# ece411-t04-filamint-V5_2.net
KiCad netlist of a schematic drawn in EAGLE
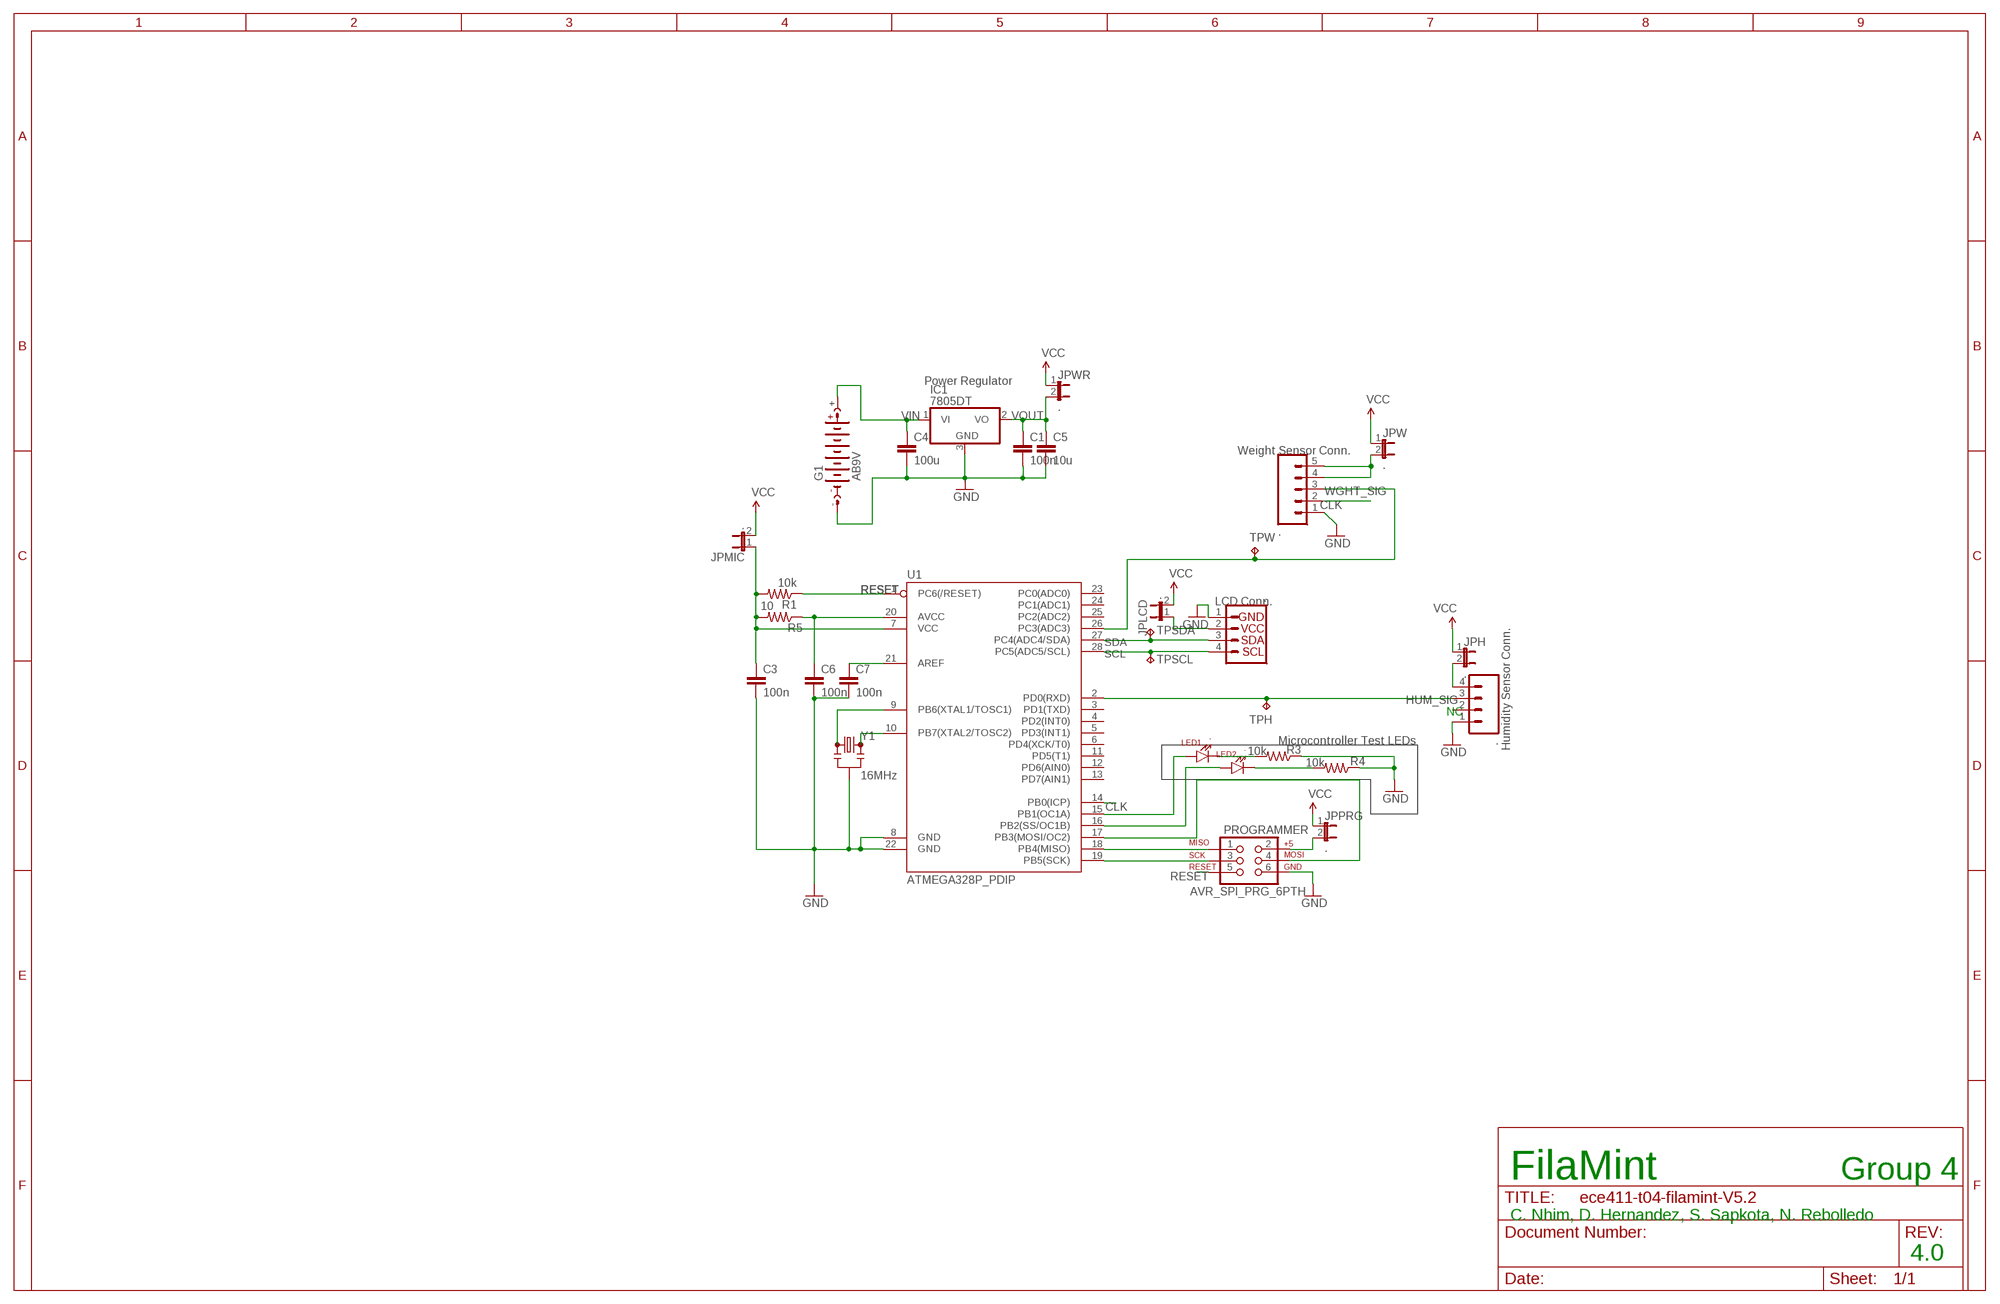
[diagram p0: schematic, sheet 1]

(export (version "E")
  (design (tool "Eeschema 10.0.6"))
  (components
    (comp (ref "C1")
      (value "100n")
      (footprint "eagle-import:C0805")
      (libsource (lib "eagle-import") (part "C-EUC0805"))
    )
    (comp (ref "C3")
      (value "100n")
      (footprint "eagle-import:C0805")
      (libsource (lib "eagle-import") (part "C-EUC0805"))
    )
    (comp (ref "C4")
      (value "100u")
      (footprint "eagle-import:C025-024X044")
      (libsource (lib "eagle-import") (part "C-EU025-024X044"))
    )
    (comp (ref "C5")
      (value "10u")
      (footprint "eagle-import:C025-024X044")
      (libsource (lib "eagle-import") (part "C-EU025-024X044"))
    )
    (comp (ref "C6")
      (value "100n")
      (footprint "eagle-import:C0805")
      (libsource (lib "eagle-import") (part "C-EUC0805"))
    )
    (comp (ref "C7")
      (value "100n")
      (footprint "eagle-import:C0805")
      (libsource (lib "eagle-import") (part "C-EUC0805"))
    )
    (comp (ref "DHT22")
      (value ".")
      (footprint "eagle-import:1X04-1MM-RA")
      (libsource (lib "eagle-import") (part "M04SMD2"))
    )
    (comp (ref "G1")
      (value "AB9V")
      (footprint "eagle-import:AB9V")
      (libsource (lib "eagle-import") (part "AB9V"))
    )
    (comp (ref "HX711")
      (value ".")
      (footprint "eagle-import:1X05-1MM")
      (libsource (lib "eagle-import") (part "M05SMD"))
    )
    (comp (ref "IC1")
      (value "7805DT")
      (footprint "eagle-import:TO252")
      (libsource (lib "eagle-import") (part "78DT05"))
    )
    (comp (ref "JPH")
      (value ".")
      (footprint "eagle-import:JP1")
      (libsource (lib "eagle-import") (part "JP1E"))
    )
    (comp (ref "JPLCD")
      (value ".")
      (footprint "eagle-import:JP1")
      (libsource (lib "eagle-import") (part "JP1E"))
    )
    (comp (ref "JPMIC")
      (value ".")
      (footprint "eagle-import:JP1")
      (libsource (lib "eagle-import") (part "JP1E"))
    )
    (comp (ref "JPPRG")
      (value ".")
      (footprint "eagle-import:JP1")
      (libsource (lib "eagle-import") (part "JP1E"))
    )
    (comp (ref "JPW")
      (value ".")
      (footprint "eagle-import:JP1")
      (libsource (lib "eagle-import") (part "JP1E"))
    )
    (comp (ref "JPWR")
      (value ".")
      (footprint "eagle-import:JP1")
      (libsource (lib "eagle-import") (part "JP1E"))
    )
    (comp (ref "LCD")
      (value ".")
      (footprint "eagle-import:1X04")
      (libsource (lib "eagle-import") (part "I2C_STANDARD"))
    )
    (comp (ref "LED1")
      (value ".")
      (footprint "eagle-import:LTE-302")
      (libsource (lib "eagle-import") (part "LTE-302"))
    )
    (comp (ref "LED2")
      (value ".")
      (footprint "eagle-import:LTE-302")
      (libsource (lib "eagle-import") (part "LTE-302"))
    )
    (comp (ref "PROGRAMMER")
      (value "AVR_SPI_PRG_6PTH")
      (footprint "eagle-import:2X3")
      (libsource (lib "eagle-import") (part "AVR_SPI_PRG_6PTH"))
    )
    (comp (ref "R1")
      (value "10k")
      (footprint "eagle-import:0204_5")
      (libsource (lib "eagle-import") (part "R-US_0204/5"))
    )
    (comp (ref "R3")
      (value "10k")
      (footprint "eagle-import:0204_5")
      (libsource (lib "eagle-import") (part "R-US_0204/5"))
    )
    (comp (ref "R4")
      (value "10k")
      (footprint "eagle-import:0204_5")
      (libsource (lib "eagle-import") (part "R-US_0204/5"))
    )
    (comp (ref "R5")
      (value "10")
      (footprint "eagle-import:0204_5")
      (libsource (lib "eagle-import") (part "R-US_0204/5"))
    )
    (comp (ref "TPH")
      (value "TPB1,27")
      (footprint "eagle-import:B1,27")
      (libsource (lib "eagle-import") (part "TPB1,27"))
    )
    (comp (ref "TPSCL")
      (value "TPB1,27")
      (footprint "eagle-import:B1,27")
      (libsource (lib "eagle-import") (part "TPB1,27"))
    )
    (comp (ref "TPSDA")
      (value "TPB1,27")
      (footprint "eagle-import:B1,27")
      (libsource (lib "eagle-import") (part "TPB1,27"))
    )
    (comp (ref "TPW")
      (value "TPB1,27")
      (footprint "eagle-import:B1,27")
      (libsource (lib "eagle-import") (part "TPB1,27"))
    )
    (comp (ref "U1")
      (value "ATMEGA328P_PDIP")
      (footprint "eagle-import:DIL28-3")
      (libsource (lib "eagle-import") (part "ATMEGA328P_PDIP"))
    )
    (comp (ref "Y1")
      (value "16MHz")
      (footprint "eagle-import:RESONATOR-PTH")
      (libsource (lib "eagle-import") (part "RESONATORPTH"))
    )
  )
  (nets
    (net (code "1") (name "/CLK") (class "Default")
      (node (ref "HX711") (pin "2") (pinfunction "2_2") (pintype "passive"))
      (node (ref "U1") (pin "14") (pinfunction "PB0(ICP)_14") (pintype "bidirectional"))
    )
    (net (code "2") (name "/HUM_SIG") (class "Default")
      (node (ref "DHT22") (pin "3") (pinfunction "3_3") (pintype "passive"))
      (node (ref "TPH") (pin "TP") (pinfunction "TP_TP") (pintype "input"))
      (node (ref "U1") (pin "2") (pinfunction "PD0(RXD)_2") (pintype "bidirectional"))
    )
    (net (code "3") (name "/RESET") (class "Default")
      (node (ref "PROGRAMMER") (pin "5") (pinfunction "5_5") (pintype "passive"))
      (node (ref "R1") (pin "1") (pinfunction "1_1") (pintype "passive"))
      (node (ref "U1") (pin "1") (pinfunction "PC6(/RESET)_1") (pintype "bidirectional"))
    )
    (net (code "4") (name "/SCL") (class "Default")
      (node (ref "LCD") (pin "4") (pinfunction "4_4") (pintype "passive"))
      (node (ref "TPSCL") (pin "TP") (pinfunction "TP_TP") (pintype "input"))
      (node (ref "U1") (pin "28") (pinfunction "PC5(ADC5/SCL)_28") (pintype "bidirectional"))
    )
    (net (code "5") (name "/SDA") (class "Default")
      (node (ref "LCD") (pin "3") (pinfunction "3_3") (pintype "passive"))
      (node (ref "TPSDA") (pin "TP") (pinfunction "TP_TP") (pintype "input"))
      (node (ref "U1") (pin "27") (pinfunction "PC4(ADC4/SDA)_27") (pintype "bidirectional"))
    )
    (net (code "6") (name "/VIN") (class "Default")
      (node (ref "C4") (pin "1") (pinfunction "1_1") (pintype "passive"))
      (node (ref "G1") (pin "+") (pinfunction "+_+") (pintype "passive"))
      (node (ref "IC1") (pin "1") (pinfunction "VI_1") (pintype "input"))
    )
    (net (code "7") (name "/WGHT_SIG") (class "Default")
      (node (ref "HX711") (pin "3") (pinfunction "3_3") (pintype "passive"))
      (node (ref "TPW") (pin "TP") (pinfunction "TP_TP") (pintype "input"))
      (node (ref "U1") (pin "26") (pinfunction "PC3(ADC3)_26") (pintype "bidirectional"))
    )
    (net (code "8") (name "GND") (class "Default")
      (node (ref "C1") (pin "2") (pinfunction "2_2") (pintype "passive"))
      (node (ref "C3") (pin "2") (pinfunction "2_2") (pintype "passive"))
      (node (ref "C4") (pin "2") (pinfunction "2_2") (pintype "passive"))
      (node (ref "C5") (pin "2") (pinfunction "2_2") (pintype "passive"))
      (node (ref "C6") (pin "2") (pinfunction "2_2") (pintype "passive"))
      (node (ref "C7") (pin "2") (pinfunction "2_2") (pintype "passive"))
      (node (ref "DHT22") (pin "1") (pinfunction "1_1") (pintype "passive"))
      (node (ref "G1") (pin "-") (pinfunction "-_-") (pintype "passive"))
      (node (ref "HX711") (pin "1") (pinfunction "1_1") (pintype "passive"))
      (node (ref "IC1") (pin "3") (pinfunction "GND_3") (pintype "passive"))
      (node (ref "LCD") (pin "1") (pinfunction "1_1") (pintype "passive"))
      (node (ref "PROGRAMMER") (pin "6") (pinfunction "6_6") (pintype "passive"))
      (node (ref "R3") (pin "1") (pinfunction "1_1") (pintype "passive"))
      (node (ref "R4") (pin "1") (pinfunction "1_1") (pintype "passive"))
      (node (ref "U1") (pin "22") (pinfunction "GND_22") (pintype "bidirectional"))
      (node (ref "U1") (pin "8") (pinfunction "GND_8") (pintype "bidirectional"))
      (node (ref "Y1") (pin "2") (pinfunction "2_2") (pintype "passive"))
    )
    (net (code "9") (name "Net-(DHT22-Pad4)") (class "Default")
      (node (ref "DHT22") (pin "4") (pinfunction "4_4") (pintype "passive"))
      (node (ref "JPH") (pin "2") (pinfunction "2_2") (pintype "passive"))
    )
    (net (code "10") (name "Net-(HX711-Pad4)") (class "Default")
      (node (ref "HX711") (pin "4") (pinfunction "4_4") (pintype "passive"))
      (node (ref "HX711") (pin "5") (pinfunction "5_5") (pintype "passive"))
      (node (ref "JPW") (pin "2") (pinfunction "2_2") (pintype "passive"))
    )
    (net (code "11") (name "Net-(IC1-VO)") (class "Default")
      (node (ref "C1") (pin "1") (pinfunction "1_1") (pintype "passive"))
      (node (ref "C5") (pin "1") (pinfunction "1_1") (pintype "passive"))
      (node (ref "IC1") (pin "2") (pinfunction "VO_2") (pintype "passive"))
      (node (ref "JPWR") (pin "2") (pinfunction "2_2") (pintype "passive"))
    )
    (net (code "12") (name "Net-(JPLCD-Pad1)") (class "Default")
      (node (ref "JPLCD") (pin "1") (pinfunction "1_1") (pintype "passive"))
      (node (ref "LCD") (pin "2") (pinfunction "2_2") (pintype "passive"))
    )
    (net (code "13") (name "Net-(JPPRG-Pad2)") (class "Default")
      (node (ref "JPPRG") (pin "2") (pinfunction "2_2") (pintype "passive"))
      (node (ref "PROGRAMMER") (pin "2") (pinfunction "2_2") (pintype "passive"))
    )
    (net (code "14") (name "Net-(LED1-PadC)") (class "Default")
      (node (ref "LED1") (pin "C") (pinfunction "C_C") (pintype "bidirectional"))
      (node (ref "R3") (pin "2") (pinfunction "2_2") (pintype "passive"))
    )
    (net (code "15") (name "Net-(LED2-PadC)") (class "Default")
      (node (ref "LED2") (pin "C") (pinfunction "C_C") (pintype "bidirectional"))
      (node (ref "R4") (pin "2") (pinfunction "2_2") (pintype "passive"))
    )
    (net (code "16") (name "Net-(U1-AREF)") (class "Default")
      (node (ref "C7") (pin "1") (pinfunction "1_1") (pintype "passive"))
      (node (ref "U1") (pin "21") (pinfunction "AREF_21") (pintype "bidirectional"))
    )
    (net (code "17") (name "Net-(U1-AVCC)") (class "Default")
      (node (ref "C6") (pin "1") (pinfunction "1_1") (pintype "passive"))
      (node (ref "R5") (pin "1") (pinfunction "1_1") (pintype "passive"))
      (node (ref "U1") (pin "20") (pinfunction "AVCC_20") (pintype "bidirectional"))
    )
    (net (code "18") (name "Net-(U1-PB1(OC1A))") (class "Default")
      (node (ref "LED1") (pin "A") (pinfunction "A_A") (pintype "bidirectional"))
      (node (ref "U1") (pin "15") (pinfunction "PB1(OC1A)_15") (pintype "bidirectional"))
    )
    (net (code "19") (name "Net-(U1-PB2(SS{slash}OC1B))") (class "Default")
      (node (ref "LED2") (pin "A") (pinfunction "A_A") (pintype "bidirectional"))
      (node (ref "U1") (pin "16") (pinfunction "PB2(SS/OC1B)_16") (pintype "bidirectional"))
    )
    (net (code "20") (name "Net-(U1-PB3(MOSI{slash}OC2))") (class "Default")
      (node (ref "PROGRAMMER") (pin "4") (pinfunction "4_4") (pintype "passive"))
      (node (ref "U1") (pin "17") (pinfunction "PB3(MOSI/OC2)_17") (pintype "bidirectional"))
    )
    (net (code "21") (name "Net-(U1-PB4(MISO))") (class "Default")
      (node (ref "PROGRAMMER") (pin "1") (pinfunction "1_1") (pintype "passive"))
      (node (ref "U1") (pin "18") (pinfunction "PB4(MISO)_18") (pintype "bidirectional"))
    )
    (net (code "22") (name "Net-(U1-PB5(SCK))") (class "Default")
      (node (ref "PROGRAMMER") (pin "3") (pinfunction "3_3") (pintype "passive"))
      (node (ref "U1") (pin "19") (pinfunction "PB5(SCK)_19") (pintype "bidirectional"))
    )
    (net (code "23") (name "Net-(U1-PB6(XTAL1{slash}TOSC1))") (class "Default")
      (node (ref "U1") (pin "9") (pinfunction "PB6(XTAL1/TOSC1)_9") (pintype "bidirectional"))
      (node (ref "Y1") (pin "1") (pinfunction "1_1") (pintype "passive"))
    )
    (net (code "24") (name "Net-(U1-PB7(XTAL2{slash}TOSC2))") (class "Default")
      (node (ref "U1") (pin "10") (pinfunction "PB7(XTAL2/TOSC2)_10") (pintype "bidirectional"))
      (node (ref "Y1") (pin "3") (pinfunction "3_3") (pintype "passive"))
    )
    (net (code "25") (name "Net-(U1-VCC)") (class "Default")
      (node (ref "C3") (pin "1") (pinfunction "1_1") (pintype "passive"))
      (node (ref "JPMIC") (pin "1") (pinfunction "1_1") (pintype "passive"))
      (node (ref "R1") (pin "2") (pinfunction "2_2") (pintype "passive"))
      (node (ref "R5") (pin "2") (pinfunction "2_2") (pintype "passive"))
      (node (ref "U1") (pin "7") (pinfunction "VCC_7") (pintype "bidirectional"))
    )
    (net (code "26") (name "VCC") (class "Default")
      (node (ref "JPH") (pin "1") (pinfunction "1_1") (pintype "passive"))
      (node (ref "JPLCD") (pin "2") (pinfunction "2_2") (pintype "passive"))
      (node (ref "JPMIC") (pin "2") (pinfunction "2_2") (pintype "passive"))
      (node (ref "JPPRG") (pin "1") (pinfunction "1_1") (pintype "passive"))
      (node (ref "JPW") (pin "1") (pinfunction "1_1") (pintype "passive"))
      (node (ref "JPWR") (pin "1") (pinfunction "1_1") (pintype "passive"))
    )
    (net (code "27") (name "unconnected-(DHT22-Pad2)") (class "Default")
      (node (ref "DHT22") (pin "2") (pinfunction "2_2") (pintype "passive"))
    )
    (net (code "28") (name "unconnected-(U1-PC0(ADC0)-Pad23)") (class "Default")
      (node (ref "U1") (pin "23") (pinfunction "PC0(ADC0)_23") (pintype "bidirectional"))
    )
    (net (code "29") (name "unconnected-(U1-PC1(ADC1)-Pad24)") (class "Default")
      (node (ref "U1") (pin "24") (pinfunction "PC1(ADC1)_24") (pintype "bidirectional"))
    )
    (net (code "30") (name "unconnected-(U1-PC2(ADC2)-Pad25)") (class "Default")
      (node (ref "U1") (pin "25") (pinfunction "PC2(ADC2)_25") (pintype "bidirectional"))
    )
    (net (code "31") (name "unconnected-(U1-PD1(TXD)-Pad3)") (class "Default")
      (node (ref "U1") (pin "3") (pinfunction "PD1(TXD)_3") (pintype "bidirectional"))
    )
    (net (code "32") (name "unconnected-(U1-PD2(INT0)-Pad4)") (class "Default")
      (node (ref "U1") (pin "4") (pinfunction "PD2(INT0)_4") (pintype "bidirectional"))
    )
    (net (code "33") (name "unconnected-(U1-PD3(INT1)-Pad5)") (class "Default")
      (node (ref "U1") (pin "5") (pinfunction "PD3(INT1)_5") (pintype "bidirectional"))
    )
    (net (code "34") (name "unconnected-(U1-PD4(XCK{slash}T0)-Pad6)") (class "Default")
      (node (ref "U1") (pin "6") (pinfunction "PD4(XCK/T0)_6") (pintype "bidirectional"))
    )
    (net (code "35") (name "unconnected-(U1-PD5(T1)-Pad11)") (class "Default")
      (node (ref "U1") (pin "11") (pinfunction "PD5(T1)_11") (pintype "bidirectional"))
    )
    (net (code "36") (name "unconnected-(U1-PD6(AIN0)-Pad12)") (class "Default")
      (node (ref "U1") (pin "12") (pinfunction "PD6(AIN0)_12") (pintype "bidirectional"))
    )
    (net (code "37") (name "unconnected-(U1-PD7(AIN1)-Pad13)") (class "Default")
      (node (ref "U1") (pin "13") (pinfunction "PD7(AIN1)_13") (pintype "bidirectional"))
    )
  )
)
